# EPS_MPPT_Y_EMI-Filter_Out.net
KiCad netlist of a schematic drawn in Altium Designer
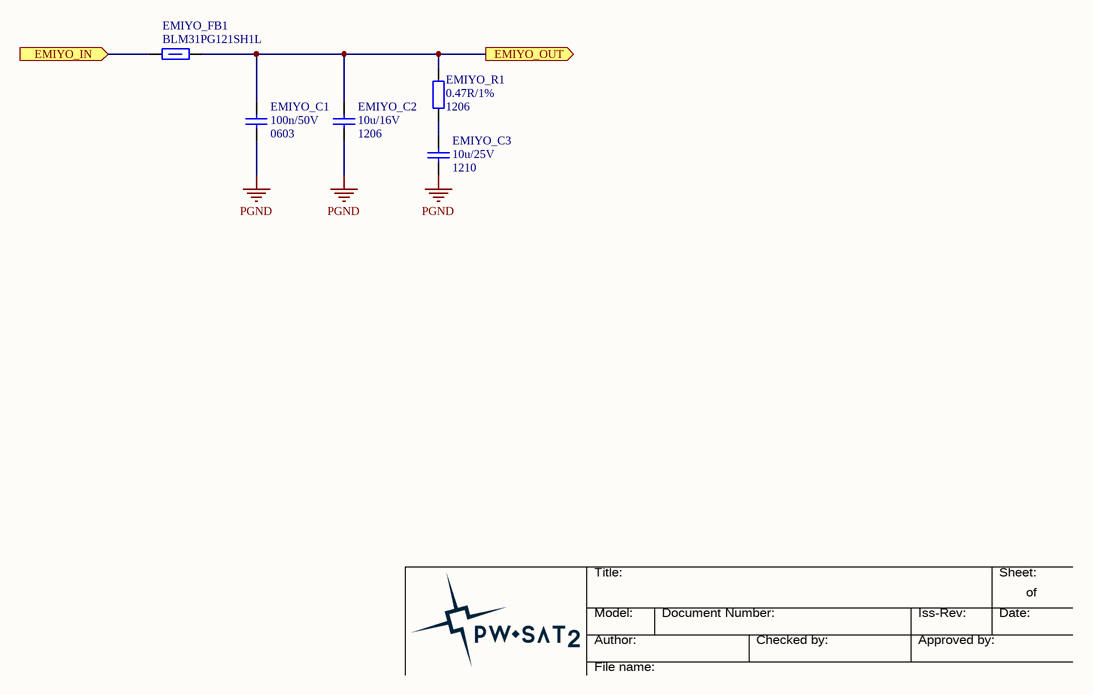
[diagram p0: EPS_MPPT_Y_EMI-Filter_Out.SchDoc]

(export (version "E")
  (design (tool "Eeschema 10.0.6"))
  (components
    (comp (ref "EMIYO_C1")
      (value "100n/50V")
      (footprint "SMD_Capacitor_0603")
      (description "Ceramic Cap Kemet COTS 100n/50V X7R 0603")
      (fields
        (field (name "MANUFACTURER") "Kemet")
        (field (name "MANUFACTURERPARTNUMBER") "C0603T104K5RALTU")
        (field (name "PACKAGE") "0603")
      )
      (libsource (lib "capacitors") (part "Cer_C0603T104K5RALTU"))
    )
    (comp (ref "EMIYO_C2")
      (value "10u/16V")
      (footprint "SMD_Capacitor_1206")
      (description "Ceramic Cap Kemet COTS 10u/16V X7R 1206")
      (fields
        (field (name "MANUFACTURERPARTNUMBER") "C1206T106K4RACTU")
        (field (name "MANUFACTURER") "Kemet")
        (field (name "PACKGE") "1206")
      )
      (libsource (lib "capacitors") (part "Cer_C1206T106K4RACTU"))
    )
    (comp (ref "EMIYO_C3")
      (value "10u/25V")
      (footprint "SMD_Capacitor_1210")
      (description "Ceramic Cap Murata Automotive 10u/25V X7R 1210")
      (fields
        (field (name "MANUFACTURER") "Murata")
        (field (name "MANUFACTURERPARTNUMBER") "GCJ32ER71E106KA12L")
        (field (name "PACKAGE") "1210")
      )
      (libsource (lib "capacitors") (part "Cer_GCJ32ER71E106KA12L"))
    )
    (comp (ref "EMIYO_FB1")
      (value "120R/100MHz")
      (footprint "SMD_FerriteBead_1206")
      (description "Ferrite bead, 1206, 0.02HM, 3.5A.")
      (fields (field (name "MANUFACTURER") "Murata") (field (name "MANUFACTURERPARTNUMBER") "BLM31PG121SH1L"))
      (libsource (lib "inductors") (part "BLM31PG121SH1L"))
    )
    (comp (ref "EMIYO_R1")
      (value "0.47R/1%")
      (footprint "SMD_Resistor_1206")
      (description "Panasonic Resistor 0.47R 1% 1206 330mW")
      (fields
        (field (name "MANUFACTURERPARTNUMBER") "ERJ-8BQFR47V")
        (field (name "MANUFACTURER") "Panasonic")
        (field (name "PACKAGE") "1206")
      )
      (libsource (lib "resistors") (part "ERJ-8BQFR47V"))
    )
  )
  (nets
    (net (code "1") (name "/EMIYO_IN") (class "Default")
      (node (ref "EMIYO_FB1") (pin "2") (pinfunction "2_2") (pintype "passive"))
    )
    (net (code "2") (name "/EMIYO_OUT") (class "Default")
      (node (ref "EMIYO_C1") (pin "1") (pinfunction "1_1") (pintype "passive"))
      (node (ref "EMIYO_C2") (pin "1") (pinfunction "1_1") (pintype "passive"))
      (node (ref "EMIYO_FB1") (pin "1") (pinfunction "1_1") (pintype "passive"))
      (node (ref "EMIYO_R1") (pin "2") (pinfunction "2_2") (pintype "passive"))
    )
    (net (code "3") (name "Net-(EMIYO_C3-Pad1)") (class "Default")
      (node (ref "EMIYO_C3") (pin "1") (pinfunction "1_1") (pintype "passive"))
      (node (ref "EMIYO_R1") (pin "1") (pinfunction "1_1") (pintype "passive"))
    )
    (net (code "4") (name "PGND") (class "Default")
      (node (ref "EMIYO_C1") (pin "2") (pinfunction "2_2") (pintype "passive"))
      (node (ref "EMIYO_C2") (pin "2") (pinfunction "2_2") (pintype "passive"))
      (node (ref "EMIYO_C3") (pin "2") (pinfunction "2_2") (pintype "passive"))
    )
  )
)
